# JHZ-E01S-HW-Drive-HI-S0_1-.net
KiCad netlist of a schematic drawn in Altium Designer
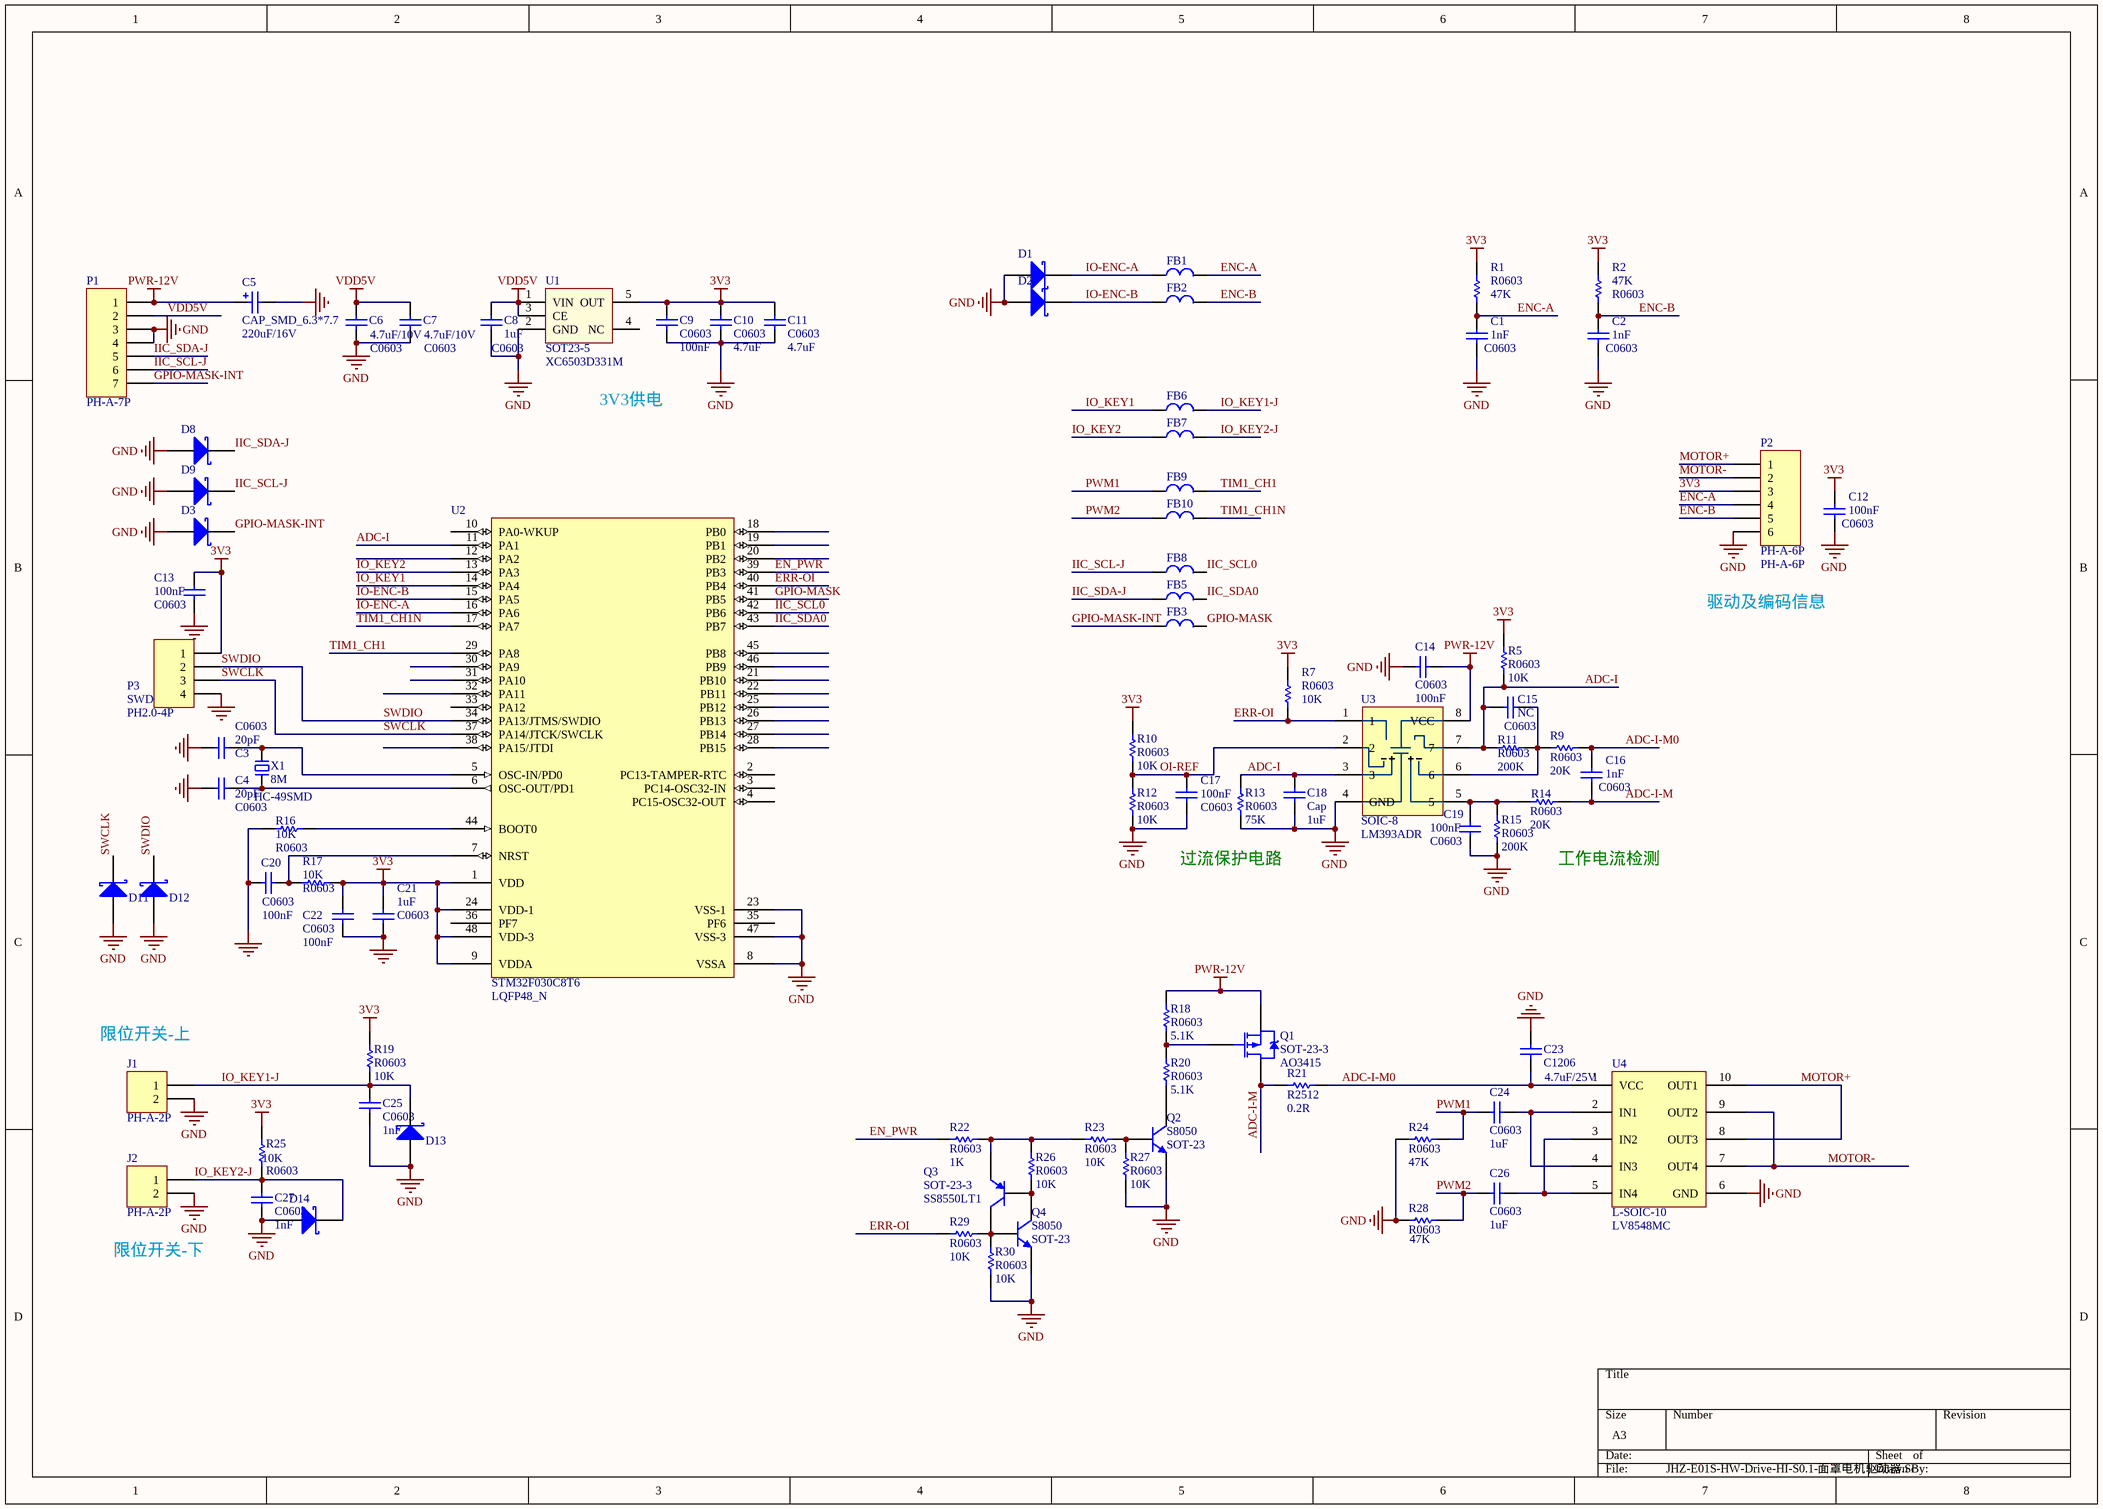
[diagram p0: JHZ-E01S-HW-Drive-HI-S0.1-面罩电机驱动器.SchDoc]

(export (version "E")
  (design (tool "Eeschema 10.0.6"))
  (components
    (comp (ref "C1")
      (value "C0603")
      (footprint "C0603_M1608")
      (description "Multilayer Ceramic Capacitor 0603")
      (fields (field (name "ALTIUM_VALUE") "1nF"))
      (libsource (lib "1.电阻、电容、电感原理库") (part "MCC0603"))
    )
    (comp (ref "C2")
      (value "C0603")
      (footprint "C0603_M1608")
      (description "Multilayer Ceramic Capacitor 0603")
      (fields (field (name "ALTIUM_VALUE") "1nF"))
      (libsource (lib "1.电阻、电容、电感原理库") (part "MCC0603"))
    )
    (comp (ref "C3")
      (value "C0603")
      (footprint "C0603_M1608")
      (description "Capacitor")
      (fields (field (name "ALTIUM_VALUE") "20pF") (field (name "PUBLISHER") "Altium Limited"))
      (libsource (lib "Miscellaneous Devices") (part "Cap"))
    )
    (comp (ref "C4")
      (value "C0603")
      (footprint "C0603_M1608")
      (description "Capacitor")
      (fields (field (name "ALTIUM_VALUE") "20pF") (field (name "PUBLISHER") "Altium Limited"))
      (libsource (lib "Miscellaneous Devices") (part "Cap"))
    )
    (comp (ref "C5")
      (value "CAP_SMD_6.3*7.7")
      (footprint "CAP_SMD_6.3*7.7")
      (description "SMD Capacitor 6.3*7.7")
      (fields (field (name "ALTIUM_VALUE") "220uF/16V"))
      (libsource (lib "1.电阻、电容、电感原理库") (part "CAP_SMD_6.3*7.7"))
    )
    (comp (ref "C6")
      (value "C0603")
      (footprint "C0603_M1608")
      (description "Capacitor")
      (fields (field (name "ALTIUM_VALUE") "4.7uF/10V") (field (name "PUBLISHER") "Altium Limited"))
      (libsource (lib "Miscellaneous Devices") (part "Cap"))
    )
    (comp (ref "C7")
      (value "C0603")
      (footprint "C0603_M1608")
      (description "Capacitor")
      (fields (field (name "ALTIUM_VALUE") "4.7uF/10V") (field (name "PUBLISHER") "Altium Limited"))
      (libsource (lib "Miscellaneous Devices") (part "Cap"))
    )
    (comp (ref "C8")
      (value "C0603")
      (footprint "C0603_M1608")
      (description "Capacitor")
      (fields (field (name "ALTIUM_VALUE") "1uF") (field (name "PUBLISHER") "Altium Limited"))
      (libsource (lib "Miscellaneous Devices") (part "Cap"))
    )
    (comp (ref "C9")
      (value "C0603")
      (footprint "C0603_M1608")
      (description "Capacitor")
      (fields (field (name "ALTIUM_VALUE") "100nF") (field (name "PUBLISHER") "Altium Limited"))
      (libsource (lib "Miscellaneous Devices") (part "Cap"))
    )
    (comp (ref "C10")
      (value "C0603")
      (footprint "C0603_M1608")
      (description "Capacitor")
      (fields (field (name "ALTIUM_VALUE") "4.7uF") (field (name "PUBLISHER") "Altium Limited"))
      (libsource (lib "Miscellaneous Devices") (part "Cap"))
    )
    (comp (ref "C11")
      (value "C0603")
      (footprint "C0603_M1608")
      (description "Capacitor")
      (fields (field (name "ALTIUM_VALUE") "4.7uF") (field (name "PUBLISHER") "Altium Limited"))
      (libsource (lib "Miscellaneous Devices") (part "Cap"))
    )
    (comp (ref "C12")
      (value "C0603")
      (footprint "C0603_M1608")
      (description "Multilayer Ceramic Capacitor 0603")
      (fields (field (name "ALTIUM_VALUE") "100nF"))
      (libsource (lib "1.电阻、电容、电感原理库") (part "MCC0603"))
    )
    (comp (ref "C13")
      (value "C0603")
      (footprint "C0603_M1608")
      (description "Capacitor")
      (fields (field (name "ALTIUM_VALUE") "100nF") (field (name "PUBLISHER") "Altium Limited"))
      (libsource (lib "Miscellaneous Devices") (part "Cap"))
    )
    (comp (ref "C14")
      (value "C0603")
      (footprint "C0603_M1608")
      (description "Multilayer Ceramic Capacitor 0603")
      (fields (field (name "ALTIUM_VALUE") "100nF"))
      (libsource (lib "1.电阻、电容、电感原理库") (part "MCC0603"))
    )
    (comp (ref "C15")
      (value "C0603")
      (footprint "C0603_M1608")
      (description "Multilayer Ceramic Capacitor 0603")
      (fields (field (name "ALTIUM_VALUE") "NC"))
      (libsource (lib "1.电阻、电容、电感原理库") (part "MCC0603"))
    )
    (comp (ref "C16")
      (value "C0603")
      (footprint "C0603_M1608")
      (description "Multilayer Ceramic Capacitor 0603")
      (fields (field (name "ALTIUM_VALUE") "1nF"))
      (libsource (lib "1.电阻、电容、电感原理库") (part "MCC0603"))
    )
    (comp (ref "C17")
      (value "C0603")
      (footprint "C0603_M1608")
      (description "Multilayer Ceramic Capacitor 0603")
      (fields (field (name "ALTIUM_VALUE") "100nF"))
      (libsource (lib "1.电阻、电容、电感原理库") (part "MCC0603"))
    )
    (comp (ref "C18")
      (value "Cap")
      (footprint "C0603_M1608")
      (description "Capacitor")
      (fields (field (name "ALTIUM_VALUE") "1uF") (field (name "PUBLISHER") "Altium Limited"))
      (libsource (lib "Miscellaneous Devices") (part "Cap"))
    )
    (comp (ref "C19")
      (value "C0603")
      (footprint "C0603_M1608")
      (description "Multilayer Ceramic Capacitor 0603")
      (fields (field (name "ALTIUM_VALUE") "100nF"))
      (libsource (lib "1.电阻、电容、电感原理库") (part "MCC0603"))
    )
    (comp (ref "C20")
      (value "C0603")
      (footprint "C0603_M1608")
      (description "Capacitor")
      (fields (field (name "ALTIUM_VALUE") "100nF") (field (name "PUBLISHER") "Altium Limited"))
      (libsource (lib "Miscellaneous Devices") (part "Cap"))
    )
    (comp (ref "C21")
      (value "C0603")
      (footprint "C0603_M1608")
      (description "Capacitor")
      (fields (field (name "ALTIUM_VALUE") "1uF") (field (name "PUBLISHER") "Altium Limited"))
      (libsource (lib "Miscellaneous Devices") (part "Cap"))
    )
    (comp (ref "C22")
      (value "C0603")
      (footprint "C0603_M1608")
      (description "Capacitor")
      (fields (field (name "ALTIUM_VALUE") "100nF") (field (name "PUBLISHER") "Altium Limited"))
      (libsource (lib "Miscellaneous Devices") (part "Cap"))
    )
    (comp (ref "C23")
      (value "C1206")
      (footprint "C1206_M3216")
      (description "Capacitor")
      (fields (field (name "ALTIUM_VALUE") "4.7uF/25V") (field (name "PUBLISHER") "Altium Limited"))
      (libsource (lib "Miscellaneous Devices") (part "Cap"))
    )
    (comp (ref "C24")
      (value "C0603")
      (footprint "C0603_M1608")
      (description "Capacitor")
      (fields (field (name "ALTIUM_VALUE") "1uF") (field (name "PUBLISHER") "Altium Limited"))
      (libsource (lib "Miscellaneous Devices") (part "Cap"))
    )
    (comp (ref "C25")
      (value "C0603")
      (footprint "C0603_M1608")
      (description "Capacitor")
      (fields (field (name "ALTIUM_VALUE") "1nF") (field (name "PUBLISHER") "Altium Limited"))
      (libsource (lib "Miscellaneous Devices") (part "Cap"))
    )
    (comp (ref "C26")
      (value "C0603")
      (footprint "C0603_M1608")
      (description "Capacitor")
      (fields (field (name "ALTIUM_VALUE") "1uF") (field (name "PUBLISHER") "Altium Limited"))
      (libsource (lib "Miscellaneous Devices") (part "Cap"))
    )
    (comp (ref "C27")
      (value "C0603")
      (footprint "C0603_M1608")
      (description "Capacitor")
      (fields (field (name "ALTIUM_VALUE") "1nF") (field (name "PUBLISHER") "Altium Limited"))
      (libsource (lib "Miscellaneous Devices") (part "Cap"))
    )
    (comp (ref "D1")
      (value "SOD-523")
      (footprint "SOD-523")
      (description "2.0A SURFACE MOUNT SCHOTTKY BARRIER  RECTIFIERS")
      (libsource (lib "2.二极管原理库") (part "SK2B"))
    )
    (comp (ref "D2")
      (value "SOD-523")
      (footprint "SOD-523")
      (description "2.0A SURFACE MOUNT SCHOTTKY BARRIER  RECTIFIERS")
      (libsource (lib "2.二极管原理库") (part "SK2B"))
    )
    (comp (ref "D3")
      (value "SOD-523")
      (footprint "SOD-523")
      (description "2.0A SURFACE MOUNT SCHOTTKY BARRIER  RECTIFIERS")
      (libsource (lib "2.二极管原理库") (part "SK2B"))
    )
    (comp (ref "D8")
      (value "SOD-523")
      (footprint "SOD-523")
      (description "2.0A SURFACE MOUNT SCHOTTKY BARRIER  RECTIFIERS")
      (libsource (lib "2.二极管原理库") (part "SK2B"))
    )
    (comp (ref "D9")
      (value "SOD-523")
      (footprint "SOD-523")
      (description "2.0A SURFACE MOUNT SCHOTTKY BARRIER  RECTIFIERS")
      (libsource (lib "2.二极管原理库") (part "SK2B"))
    )
    (comp (ref "D11")
      (value "SOD-523")
      (footprint "SOD-523")
      (description "2.0A SURFACE MOUNT SCHOTTKY BARRIER  RECTIFIERS")
      (libsource (lib "2.二极管原理库") (part "SK2B"))
    )
    (comp (ref "D12")
      (value "SOD-523")
      (footprint "SOD-523")
      (description "2.0A SURFACE MOUNT SCHOTTKY BARRIER  RECTIFIERS")
      (libsource (lib "2.二极管原理库") (part "SK2B"))
    )
    (comp (ref "D13")
      (value "SOD-523")
      (footprint "SOD-523")
      (description "2.0A SURFACE MOUNT SCHOTTKY BARRIER  RECTIFIERS")
      (libsource (lib "2.二极管原理库") (part "SK2B"))
    )
    (comp (ref "D14")
      (value "SOD-523")
      (footprint "SOD-523")
      (description "2.0A SURFACE MOUNT SCHOTTKY BARRIER  RECTIFIERS")
      (libsource (lib "2.二极管原理库") (part "SK2B"))
    )
    (comp (ref "FB1")
      (value "FBM1608-0E0PT")
      (footprint "R0603_M1608")
      (description "磁珠Ferrite Bead")
      (libsource (lib "1.电阻、电容、电感原理库") (part "FBM1608-0E0PT"))
    )
    (comp (ref "FB2")
      (value "FBM1608-0E0PT")
      (footprint "R0603_M1608")
      (description "磁珠Ferrite Bead")
      (libsource (lib "1.电阻、电容、电感原理库") (part "FBM1608-0E0PT"))
    )
    (comp (ref "FB3")
      (value "FBM1608-0E0PT")
      (footprint "R0603_M1608")
      (description "磁珠Ferrite Bead")
      (libsource (lib "1.电阻、电容、电感原理库") (part "FBM1608-0E0PT"))
    )
    (comp (ref "FB5")
      (value "FBM1608-0E0PT")
      (footprint "R0603_M1608")
      (description "磁珠Ferrite Bead")
      (libsource (lib "1.电阻、电容、电感原理库") (part "FBM1608-0E0PT"))
    )
    (comp (ref "FB6")
      (value "FBM1608-0E0PT")
      (footprint "R0603_M1608")
      (description "磁珠Ferrite Bead")
      (libsource (lib "1.电阻、电容、电感原理库") (part "FBM1608-0E0PT"))
    )
    (comp (ref "FB7")
      (value "FBM1608-0E0PT")
      (footprint "R0603_M1608")
      (description "磁珠Ferrite Bead")
      (libsource (lib "1.电阻、电容、电感原理库") (part "FBM1608-0E0PT"))
    )
    (comp (ref "FB8")
      (value "FBM1608-0E0PT")
      (footprint "R0603_M1608")
      (description "磁珠Ferrite Bead")
      (libsource (lib "1.电阻、电容、电感原理库") (part "FBM1608-0E0PT"))
    )
    (comp (ref "FB9")
      (value "FBM1608-0E0PT")
      (footprint "R0603_M1608")
      (description "磁珠Ferrite Bead")
      (libsource (lib "1.电阻、电容、电感原理库") (part "FBM1608-0E0PT"))
    )
    (comp (ref "FB10")
      (value "FBM1608-0E0PT")
      (footprint "R0603_M1608")
      (description "磁珠Ferrite Bead")
      (libsource (lib "1.电阻、电容、电感原理库") (part "FBM1608-0E0PT"))
    )
    (comp (ref "J1")
      (value "PH-A-2P")
      (footprint "PH-A-2P")
      (description "Header, 2.0mm,2-Pin")
      (libsource (lib "7.PH XH VH KF2510连接器原理库") (part "PH-A-2P"))
    )
    (comp (ref "J2")
      (value "PH-A-2P")
      (footprint "PH-A-2P")
      (description "Header, 2.0mm,2-Pin")
      (libsource (lib "7.PH XH VH KF2510连接器原理库") (part "PH-A-2P"))
    )
    (comp (ref "P1")
      (value "PH-A-7P")
      (footprint "PH-A-7P")
      (description "Header, 2.0mm,7-Pin")
      (libsource (lib "7.PH XH VH KF2510连接器原理库") (part "PH-A-7P"))
    )
    (comp (ref "P2")
      (value "PH-A-6P")
      (footprint "PH-A-6P")
      (description "Header, 2.0mm,6-Pin")
      (fields (field (name "ALTIUM_VALUE") "PH-A-6P"))
      (libsource (lib "7.PH XH VH KF2510连接器原理库") (part "PH-A-6P"))
    )
    (comp (ref "P3")
      (value "PH2.0-4P")
      (footprint "PH-A-4P")
      (description "Header, 4-Pin")
      (fields (field (name "ALTIUM_VALUE") "SWD") (field (name "PUBLISHER") "Altium Limited"))
      (libsource (lib "Miscellaneous Connectors") (part "Header 4"))
    )
    (comp (ref "Q1")
      (value "SOT-23-3")
      (footprint "SOT-23-3")
      (description "P-Channel MOSFET")
      (fields (field (name "ALTIUM_VALUE") "AO3415"))
      (libsource (lib "3.三极管原理库") (part "AO3415"))
    )
    (comp (ref "Q2")
      (value "SOT-23")
      (footprint "SOT-23_L")
      (description "NPN Bipolar Transistor")
      (fields (field (name "ALTIUM_VALUE") "S8050") (field (name "PUBLISHER") "Altium Limited"))
      (libsource (lib "CYSchlib") (part "NPN"))
    )
    (comp (ref "Q3")
      (value "SOT-23-3")
      (footprint "SOT-23-3")
      (description "PNP Bipolar Transistor")
      (fields (field (name "ALTIUM_VALUE") "SS8550LT1"))
      (libsource (lib "3.三极管原理库") (part "SS8550LT1"))
    )
    (comp (ref "Q4")
      (value "SOT-23")
      (footprint "SOT-23_L")
      (description "NPN Bipolar Transistor")
      (fields (field (name "ALTIUM_VALUE") "S8050") (field (name "PUBLISHER") "Altium Limited"))
      (libsource (lib "CYSchlib") (part "NPN"))
    )
    (comp (ref "R1")
      (value "R0603")
      (footprint "R0603_M1608")
      (description "Resistor")
      (fields (field (name "ALTIUM_VALUE") "47K") (field (name "PUBLISHER") "Altium Limited"))
      (libsource (lib "Miscellaneous Devices") (part "Res1"))
    )
    (comp (ref "R2")
      (value "R0603")
      (footprint "R0603_M1608")
      (description "Resistor")
      (fields (field (name "ALTIUM_VALUE") "47K") (field (name "PUBLISHER") "Altium Limited"))
      (libsource (lib "Miscellaneous Devices") (part "Res1"))
    )
    (comp (ref "R5")
      (value "R0603")
      (footprint "R0603_M1608")
      (description "Resistor")
      (fields (field (name "ALTIUM_VALUE") "10K"))
      (libsource (lib "1.电阻、电容、电感原理库") (part "R0603_M1608"))
    )
    (comp (ref "R7")
      (value "R0603")
      (description "Resistor")
      (fields (field (name "ALTIUM_VALUE") "10K") (field (name "PUBLISHER") "Altium Limited"))
      (libsource (lib "Miscellaneous Devices") (part "Res1"))
    )
    (comp (ref "R9")
      (value "R0603")
      (footprint "R0603_M1608")
      (description "Resistor")
      (fields (field (name "ALTIUM_VALUE") "20K"))
      (libsource (lib "1.电阻、电容、电感原理库") (part "R0603_M1608"))
    )
    (comp (ref "R10")
      (value "R0603")
      (footprint "R0603_M1608")
      (description "Resistor")
      (fields (field (name "ALTIUM_VALUE") "10K"))
      (libsource (lib "1.电阻、电容、电感原理库") (part "R0603_M1608"))
    )
    (comp (ref "R11")
      (value "R0603")
      (footprint "R0603_M1608")
      (description "Resistor")
      (fields (field (name "ALTIUM_VALUE") "200K"))
      (libsource (lib "1.电阻、电容、电感原理库") (part "R0603_M1608"))
    )
    (comp (ref "R12")
      (value "R0603")
      (footprint "R0603_M1608")
      (description "Resistor")
      (fields (field (name "ALTIUM_VALUE") "10K"))
      (libsource (lib "1.电阻、电容、电感原理库") (part "R0603_M1608"))
    )
    (comp (ref "R13")
      (value "R0603")
      (footprint "R0603_M1608")
      (description "Resistor")
      (fields (field (name "ALTIUM_VALUE") "75K"))
      (libsource (lib "1.电阻、电容、电感原理库") (part "R0603_M1608"))
    )
    (comp (ref "R14")
      (value "R0603")
      (footprint "R0603_M1608")
      (description "Resistor")
      (fields (field (name "ALTIUM_VALUE") "20K"))
      (libsource (lib "1.电阻、电容、电感原理库") (part "R0603_M1608"))
    )
    (comp (ref "R15")
      (value "R0603")
      (footprint "R0603_M1608")
      (description "Resistor")
      (fields (field (name "ALTIUM_VALUE") "200K"))
      (libsource (lib "1.电阻、电容、电感原理库") (part "R0603_M1608"))
    )
    (comp (ref "R16")
      (value "R0603")
      (footprint "R0603_M1608")
      (description "Resistor")
      (fields (field (name "ALTIUM_VALUE") "10K") (field (name "PUBLISHER") "Altium Limited"))
      (libsource (lib "Miscellaneous Devices") (part "Res1"))
    )
    (comp (ref "R17")
      (value "R0603")
      (footprint "R0603_M1608")
      (description "Resistor")
      (fields (field (name "ALTIUM_VALUE") "10K") (field (name "PUBLISHER") "Altium Limited"))
      (libsource (lib "Miscellaneous Devices") (part "Res1"))
    )
    (comp (ref "R18")
      (value "R0603")
      (footprint "R0603_M1608")
      (description "Resistor")
      (fields (field (name "ALTIUM_VALUE") "5.1K") (field (name "PUBLISHER") "Altium Limited"))
      (libsource (lib "Miscellaneous Devices") (part "Res1"))
    )
    (comp (ref "R19")
      (value "R0603")
      (footprint "R0603_M1608")
      (description "Resistor")
      (fields (field (name "ALTIUM_VALUE") "10K") (field (name "PUBLISHER") "Altium Limited"))
      (libsource (lib "Miscellaneous Devices") (part "Res1"))
    )
    (comp (ref "R20")
      (value "R0603")
      (footprint "R0603_M1608")
      (description "Resistor")
      (fields (field (name "ALTIUM_VALUE") "5.1K") (field (name "PUBLISHER") "Altium Limited"))
      (libsource (lib "Miscellaneous Devices") (part "Res1"))
    )
    (comp (ref "R21")
      (value "R2512")
      (footprint "R2512_M6332")
      (description "Resistor")
      (fields (field (name "ALTIUM_VALUE") "0.2R") (field (name "PUBLISHER") "Altium Limited"))
      (libsource (lib "Miscellaneous Devices") (part "Res1"))
    )
    (comp (ref "R22")
      (value "R0603")
      (footprint "R0603_M1608")
      (description "Resistor")
      (fields (field (name "ALTIUM_VALUE") "1K") (field (name "PUBLISHER") "Altium Limited"))
      (libsource (lib "Miscellaneous Devices") (part "Res1"))
    )
    (comp (ref "R23")
      (value "R0603")
      (footprint "R0603_M1608")
      (description "Resistor")
      (fields (field (name "ALTIUM_VALUE") "10K") (field (name "PUBLISHER") "Altium Limited"))
      (libsource (lib "Miscellaneous Devices") (part "Res1"))
    )
    (comp (ref "R24")
      (value "R0603")
      (footprint "R0603_M1608")
      (description "Resistor")
      (fields (field (name "ALTIUM_VALUE") "47K") (field (name "PUBLISHER") "Altium Limited"))
      (libsource (lib "Miscellaneous Devices") (part "Res1"))
    )
    (comp (ref "R25")
      (value "R0603")
      (footprint "R0603_M1608")
      (description "Resistor")
      (fields (field (name "ALTIUM_VALUE") "10K") (field (name "PUBLISHER") "Altium Limited"))
      (libsource (lib "Miscellaneous Devices") (part "Res1"))
    )
    (comp (ref "R26")
      (value "R0603")
      (footprint "R0603_M1608")
      (description "Resistor")
      (fields (field (name "ALTIUM_VALUE") "10K") (field (name "PUBLISHER") "Altium Limited"))
      (libsource (lib "Miscellaneous Devices") (part "Res1"))
    )
    (comp (ref "R27")
      (value "R0603")
      (footprint "R0603_M1608")
      (description "Resistor")
      (fields (field (name "ALTIUM_VALUE") "10K") (field (name "PUBLISHER") "Altium Limited"))
      (libsource (lib "Miscellaneous Devices") (part "Res1"))
    )
    (comp (ref "R28")
      (value "R0603")
      (footprint "R0603_M1608")
      (description "Resistor")
      (fields (field (name "ALTIUM_VALUE") "47K") (field (name "PUBLISHER") "Altium Limited"))
      (libsource (lib "Miscellaneous Devices") (part "Res1"))
    )
    (comp (ref "R29")
      (value "R0603")
      (footprint "R0603_M1608")
      (description "Resistor")
      (fields (field (name "ALTIUM_VALUE") "10K") (field (name "PUBLISHER") "Altium Limited"))
      (libsource (lib "Miscellaneous Devices") (part "Res1"))
    )
    (comp (ref "R30")
      (value "R0603")
      (footprint "R0603_M1608")
      (description "Resistor")
      (fields (field (name "ALTIUM_VALUE") "10K") (field (name "PUBLISHER") "Altium Limited"))
      (libsource (lib "Miscellaneous Devices") (part "Res1"))
    )
    (comp (ref "U1")
      (value "SOT23-5")
      (footprint "SOT-23-5")
      (fields (field (name "ALTIUM_VALUE") "XC6503D331M"))
      (libsource (lib "SCH") (part "XC6503D301MR"))
    )
    (comp (ref "U2")
      (value "LQFP48_N")
      (footprint "LQFP48_N")
      (description "STM32 ARM-based 32-bit MCU with 64 Kbytes Flash, 48-pin LQFP, Industrial Temperature")
      (fields (field (name "ALTIUM_VALUE") "STM32F030C8T6") (field (name "PUBLISHER") "*"))
      (libsource (lib "ST Microcontroller 32-Bit STM32 SCH") (part "STM32F103C8T6"))
    )
    (comp (ref "U3")
      (value "SOIC-8")
      (footprint "SOIC-8")
      (description "Dual Operational Amplifiers")
      (fields (field (name "ALTIUM_VALUE") "LM393ADR"))
      (libsource (lib "5.芯片原理库") (part "LM358ADR"))
    )
    (comp (ref "U4")
      (value "L-SOIC-10")
      (footprint "L-SOIC-10")
      (fields (field (name "ALTIUM_VALUE") "LV8548MC"))
      (libsource (lib "Schlib1") (part "LV8548MC"))
    )
    (comp (ref "X1")
      (value "8M")
      (footprint "HC-49SMD")
      (fields (field (name "ALTIUM_VALUE") "HC-49SMD"))
      (libsource (lib "CYSchlib") (part "XTAL"))
    )
  )
  (nets
    (net (code "1") (name "/ADC-I") (class "Default")
      (node (ref "C15") (pin "2") (pinfunction "2_2") (pintype "passive"))
      (node (ref "C18") (pin "2") (pinfunction "2_2") (pintype "passive"))
      (node (ref "R11") (pin "1") (pinfunction "1_1") (pintype "passive"))
      (node (ref "R13") (pin "2") (pinfunction "2_2") (pintype "passive"))
      (node (ref "R5") (pin "2") (pinfunction "2_2") (pintype "passive"))
      (node (ref "U2") (pin "11") (pinfunction "PA1_11") (pintype "bidirectional"))
      (node (ref "U3") (pin "3") (pinfunction "3_3") (pintype "passive"))
      (node (ref "U3") (pin "7") (pinfunction "7_7") (pintype "passive"))
    )
    (net (code "2") (name "/ADC-I-M") (class "Default")
      (node (ref "C16") (pin "1") (pinfunction "1_1") (pintype "passive"))
      (node (ref "Q1") (pin "3") (pinfunction "D_3") (pintype "passive"))
      (node (ref "R14") (pin "1") (pinfunction "1_1") (pintype "passive"))
      (node (ref "R21") (pin "1") (pinfunction "1_1") (pintype "passive"))
    )
    (net (code "3") (name "/ADC-I-M0") (class "Default")
      (node (ref "C16") (pin "2") (pinfunction "2_2") (pintype "passive"))
      (node (ref "C23") (pin "1") (pinfunction "1_1") (pintype "passive"))
      (node (ref "R21") (pin "2") (pinfunction "2_2") (pintype "passive"))
      (node (ref "R9") (pin "1") (pinfunction "1_1") (pintype "passive"))
      (node (ref "U4") (pin "1") (pinfunction "VCC_1") (pintype "passive"))
    )
    (net (code "4") (name "/ENC-A") (class "Default")
      (node (ref "C1") (pin "1") (pinfunction "1_1") (pintype "passive"))
      (node (ref "FB1") (pin "2") (pinfunction "2_2") (pintype "passive"))
      (node (ref "P2") (pin "4") (pinfunction "4_4") (pintype "passive"))
      (node (ref "R1") (pin "1") (pinfunction "1_1") (pintype "passive"))
    )
    (net (code "5") (name "/ENC-B") (class "Default")
      (node (ref "C2") (pin "1") (pinfunction "1_1") (pintype "passive"))
      (node (ref "FB2") (pin "2") (pinfunction "2_2") (pintype "passive"))
      (node (ref "P2") (pin "5") (pinfunction "5_5") (pintype "passive"))
      (node (ref "R2") (pin "1") (pinfunction "1_1") (pintype "passive"))
    )
    (net (code "6") (name "/EN_PWR") (class "Default")
      (node (ref "R22") (pin "2") (pinfunction "2_2") (pintype "passive"))
      (node (ref "U2") (pin "39") (pinfunction "PB3_39") (pintype "bidirectional"))
    )
    (net (code "7") (name "/ERR-OI") (class "Default")
      (node (ref "R29") (pin "2") (pinfunction "2_2") (pintype "passive"))
      (node (ref "R7") (pin "1") (pinfunction "1_1") (pintype "passive"))
      (node (ref "U2") (pin "40") (pinfunction "PB4_40") (pintype "bidirectional"))
      (node (ref "U3") (pin "1") (pinfunction "1_1") (pintype "passive"))
    )
    (net (code "8") (name "/GPIO-MASK") (class "Default")
      (node (ref "FB3") (pin "2") (pinfunction "2_2") (pintype "passive"))
      (node (ref "U2") (pin "41") (pinfunction "PB5_41") (pintype "bidirectional"))
    )
    (net (code "9") (name "/GPIO-MASK-INT") (class "Default")
      (node (ref "D3") (pin "2") (pinfunction "K_2") (pintype "passive"))
      (node (ref "FB3") (pin "1") (pinfunction "1_1") (pintype "passive"))
      (node (ref "P1") (pin "7") (pinfunction "7_7") (pintype "passive"))
    )
    (net (code "10") (name "/IIC_SCL-J") (class "Default")
      (node (ref "D9") (pin "2") (pinfunction "K_2") (pintype "passive"))
      (node (ref "FB8") (pin "1") (pinfunction "1_1") (pintype "passive"))
      (node (ref "P1") (pin "6") (pinfunction "6_6") (pintype "passive"))
    )
    (net (code "11") (name "/IIC_SCL0") (class "Default")
      (node (ref "FB8") (pin "2") (pinfunction "2_2") (pintype "passive"))
      (node (ref "U2") (pin "42") (pinfunction "PB6_42") (pintype "bidirectional"))
    )
    (net (code "12") (name "/IIC_SDA-J") (class "Default")
      (node (ref "D8") (pin "2") (pinfunction "K_2") (pintype "passive"))
      (node (ref "FB5") (pin "1") (pinfunction "1_1") (pintype "passive"))
      (node (ref "P1") (pin "5") (pinfunction "5_5") (pintype "passive"))
    )
    (net (code "13") (name "/IIC_SDA0") (class "Default")
      (node (ref "FB5") (pin "2") (pinfunction "2_2") (pintype "passive"))
      (node (ref "U2") (pin "43") (pinfunction "PB7_43") (pintype "bidirectional"))
    )
    (net (code "14") (name "/IO-ENC-A") (class "Default")
      (node (ref "D1") (pin "2") (pinfunction "K_2") (pintype "passive"))
      (node (ref "FB1") (pin "1") (pinfunction "1_1") (pintype "passive"))
      (node (ref "U2") (pin "16") (pinfunction "PA6_16") (pintype "bidirectional"))
    )
    (net (code "15") (name "/IO-ENC-B") (class "Default")
      (node (ref "D2") (pin "2") (pinfunction "K_2") (pintype "passive"))
      (node (ref "FB2") (pin "1") (pinfunction "1_1") (pintype "passive"))
      (node (ref "U2") (pin "15") (pinfunction "PA5_15") (pintype "bidirectional"))
    )
    (net (code "16") (name "/IO_KEY1") (class "Default")
      (node (ref "FB6") (pin "1") (pinfunction "1_1") (pintype "passive"))
      (node (ref "U2") (pin "14") (pinfunction "PA4_14") (pintype "bidirectional"))
    )
    (net (code "17") (name "/IO_KEY1-J") (class "Default")
      (node (ref "C25") (pin "2") (pinfunction "2_2") (pintype "passive"))
      (node (ref "D13") (pin "2") (pinfunction "K_2") (pintype "passive"))
      (node (ref "FB6") (pin "2") (pinfunction "2_2") (pintype "passive"))
      (node (ref "J1") (pin "1") (pinfunction "1_1") (pintype "passive"))
      (node (ref "R19") (pin "1") (pinfunction "1_1") (pintype "passive"))
    )
    (net (code "18") (name "/IO_KEY2") (class "Default")
      (node (ref "FB7") (pin "1") (pinfunction "1_1") (pintype "passive"))
      (node (ref "U2") (pin "13") (pinfunction "PA3_13") (pintype "bidirectional"))
    )
    (net (code "19") (name "/IO_KEY2-J") (class "Default")
      (node (ref "C27") (pin "2") (pinfunction "2_2") (pintype "passive"))
      (node (ref "D14") (pin "2") (pinfunction "K_2") (pintype "passive"))
      (node (ref "FB7") (pin "2") (pinfunction "2_2") (pintype "passive"))
      (node (ref "J2") (pin "1") (pinfunction "1_1") (pintype "passive"))
      (node (ref "R25") (pin "1") (pinfunction "1_1") (pintype "passive"))
    )
    (net (code "20") (name "/MOTOR+") (class "Default")
      (node (ref "P2") (pin "1") (pinfunction "1_1") (pintype "passive"))
      (node (ref "U4") (pin "10") (pinfunction "OUT1_10") (pintype "passive"))
      (node (ref "U4") (pin "8") (pinfunction "OUT3_8") (pintype "passive"))
    )
    (net (code "21") (name "/MOTOR-") (class "Default")
      (node (ref "P2") (pin "2") (pinfunction "2_2") (pintype "passive"))
      (node (ref "U4") (pin "7") (pinfunction "OUT4_7") (pintype "passive"))
      (node (ref "U4") (pin "9") (pinfunction "OUT2_9") (pintype "passive"))
    )
    (net (code "22") (name "/OI-REF") (class "Default")
      (node (ref "C17") (pin "2") (pinfunction "2_2") (pintype "passive"))
      (node (ref "R10") (pin "1") (pinfunction "1_1") (pintype "passive"))
      (node (ref "R12") (pin "2") (pinfunction "2_2") (pintype "passive"))
      (node (ref "U3") (pin "2") (pinfunction "2_2") (pintype "passive"))
    )
    (net (code "23") (name "/PWM1") (class "Default")
      (node (ref "C24") (pin "1") (pinfunction "1_1") (pintype "passive"))
      (node (ref "FB9") (pin "1") (pinfunction "1_1") (pintype "passive"))
      (node (ref "R24") (pin "1") (pinfunction "1_1") (pintype "passive"))
    )
    (net (code "24") (name "/PWM2") (class "Default")
      (node (ref "C26") (pin "1") (pinfunction "1_1") (pintype "passive"))
      (node (ref "FB10") (pin "1") (pinfunction "1_1") (pintype "passive"))
      (node (ref "R28") (pin "1") (pinfunction "1_1") (pintype "passive"))
    )
    (net (code "25") (name "/SWCLK") (class "Default")
      (node (ref "D11") (pin "2") (pinfunction "K_2") (pintype "passive"))
      (node (ref "P3") (pin "3") (pinfunction "3_3") (pintype "passive"))
      (node (ref "U2") (pin "37") (pinfunction "PA14/JTCK/SWCLK_37") (pintype "bidirectional"))
    )
    (net (code "26") (name "/SWDIO") (class "Default")
      (node (ref "D12") (pin "2") (pinfunction "K_2") (pintype "passive"))
      (node (ref "P3") (pin "2") (pinfunction "2_2") (pintype "passive"))
      (node (ref "U2") (pin "34") (pinfunction "PA13/JTMS/SWDIO_34") (pintype "bidirectional"))
    )
    (net (code "27") (name "/TIM1_CH1") (class "Default")
      (node (ref "FB9") (pin "2") (pinfunction "2_2") (pintype "passive"))
      (node (ref "U2") (pin "29") (pinfunction "PA8_29") (pintype "bidirectional"))
    )
    (net (code "28") (name "/TIM1_CH1N") (class "Default")
      (node (ref "FB10") (pin "2") (pinfunction "2_2") (pintype "passive"))
      (node (ref "U2") (pin "17") (pinfunction "PA7_17") (pintype "bidirectional"))
    )
    (net (code "29") (name "3V3") (class "Default")
      (node (ref "C10") (pin "1") (pinfunction "1_1") (pintype "passive"))
      (node (ref "C11") (pin "1") (pinfunction "1_1") (pintype "passive"))
      (node (ref "C12") (pin "1") (pinfunction "1_1") (pintype "passive"))
      (node (ref "C13") (pin "1") (pinfunction "1_1") (pintype "passive"))
      (node (ref "C21") (pin "1") (pinfunction "1_1") (pintype "passive"))
      (node (ref "C22") (pin "1") (pinfunction "1_1") (pintype "passive"))
      (node (ref "C9") (pin "1") (pinfunction "1_1") (pintype "passive"))
      (node (ref "P2") (pin "3") (pinfunction "3_3") (pintype "passive"))
      (node (ref "P3") (pin "1") (pinfunction "1_1") (pintype "passive"))
      (node (ref "R1") (pin "2") (pinfunction "2_2") (pintype "passive"))
      (node (ref "R10") (pin "2") (pinfunction "2_2") (pintype "passive"))
      (node (ref "R17") (pin "2") (pinfunction "2_2") (pintype "passive"))
      (node (ref "R19") (pin "2") (pinfunction "2_2") (pintype "passive"))
      (node (ref "R2") (pin "2") (pinfunction "2_2") (pintype "passive"))
      (node (ref "R25") (pin "2") (pinfunction "2_2") (pintype "passive"))
      (node (ref "R5") (pin "1") (pinfunction "1_1") (pintype "passive"))
      (node (ref "R7") (pin "2") (pinfunction "2_2") (pintype "passive"))
      (node (ref "U1") (pin "5") (pinfunction "OUT_5") (pintype "passive"))
      (node (ref "U2") (pin "1") (pinfunction "VDD_1") (pintype "power_in"))
      (node (ref "U2") (pin "24") (pinfunction "VDD-1_24") (pintype "power_in"))
      (node (ref "U2") (pin "48") (pinfunction "VDD-3_48") (pintype "power_in"))
      (node (ref "U2") (pin "9") (pinfunction "VDDA_9") (pintype "power_in"))
    )
    (net (code "30") (name "GND") (class "Default")
      (node (ref "C1") (pin "2") (pinfunction "2_2") (pintype "passive"))
      (node (ref "C10") (pin "2") (pinfunction "2_2") (pintype "passive"))
      (node (ref "C11") (pin "2") (pinfunction "2_2") (pintype "passive"))
      (node (ref "C12") (pin "2") (pinfunction "2_2") (pintype "passive"))
      (node (ref "C13") (pin "2") (pinfunction "2_2") (pintype "passive"))
      (node (ref "C14") (pin "2") (pinfunction "2_2") (pintype "passive"))
      (node (ref "C17") (pin "1") (pinfunction "1_1") (pintype "passive"))
      (node (ref "C18") (pin "1") (pinfunction "1_1") (pintype "passive"))
      (node (ref "C19") (pin "1") (pinfunction "1_1") (pintype "passive"))
      (node (ref "C2") (pin "2") (pinfunction "2_2") (pintype "passive"))
      (node (ref "C20") (pin "1") (pinfunction "1_1") (pintype "passive"))
      (node (ref "C21") (pin "2") (pinfunction "2_2") (pintype "passive"))
      (node (ref "C22") (pin "2") (pinfunction "2_2") (pintype "passive"))
      (node (ref "C23") (pin "2") (pinfunction "2_2") (pintype "passive"))
      (node (ref "C25") (pin "1") (pinfunction "1_1") (pintype "passive"))
      (node (ref "C27") (pin "1") (pinfunction "1_1") (pintype "passive"))
      (node (ref "C3") (pin "1") (pinfunction "1_1") (pintype "passive"))
      (node (ref "C4") (pin "1") (pinfunction "1_1") (pintype "passive"))
      (node (ref "C5") (pin "2") (pinfunction "2_2") (pintype "passive"))
      (node (ref "C6") (pin "1") (pinfunction "1_1") (pintype "passive"))
      (node (ref "C7") (pin "1") (pinfunction "1_1") (pintype "passive"))
      (node (ref "C8") (pin "1") (pinfunction "1_1") (pintype "passive"))
      (node (ref "C9") (pin "2") (pinfunction "2_2") (pintype "passive"))
      (node (ref "D1") (pin "1") (pinfunction "A_1") (pintype "passive"))
      (node (ref "D11") (pin "1") (pinfunction "A_1") (pintype "passive"))
      (node (ref "D12") (pin "1") (pinfunction "A_1") (pintype "passive"))
      (node (ref "D13") (pin "1") (pinfunction "A_1") (pintype "passive"))
      (node (ref "D14") (pin "1") (pinfunction "A_1") (pintype "passive"))
      (node (ref "D2") (pin "1") (pinfunction "A_1") (pintype "passive"))
      (node (ref "D3") (pin "1") (pinfunction "A_1") (pintype "passive"))
      (node (ref "D8") (pin "1") (pinfunction "A_1") (pintype "passive"))
      (node (ref "D9") (pin "1") (pinfunction "A_1") (pintype "passive"))
      (node (ref "J1") (pin "2") (pinfunction "2_2") (pintype "passive"))
      (node (ref "J2") (pin "2") (pinfunction "2_2") (pintype "passive"))
      (node (ref "P1") (pin "3") (pinfunction "3_3") (pintype "passive"))
      (node (ref "P1") (pin "4") (pinfunction "4_4") (pintype "passive"))
      (node (ref "P2") (pin "6") (pinfunction "6_6") (pintype "passive"))
      (node (ref "P3") (pin "4") (pinfunction "4_4") (pintype "passive"))
      (node (ref "Q2") (pin "2") (pinfunction "E_2") (pintype "passive"))
      (node (ref "Q4") (pin "2") (pinfunction "E_2") (pintype "passive"))
      (node (ref "R12") (pin "1") (pinfunction "1_1") (pintype "passive"))
      (node (ref "R13") (pin "1") (pinfunction "1_1") (pintype "passive"))
      (node (ref "R15") (pin "1") (pinfunction "1_1") (pintype "passive"))
      (node (ref "R16") (pin "1") (pinfunction "1_1") (pintype "passive"))
      (node (ref "R24") (pin "2") (pinfunction "2_2") (pintype "passive"))
      (node (ref "R27") (pin "1") (pinfunction "1_1") (pintype "passive"))
      (node (ref "R28") (pin "2") (pinfunction "2_2") (pintype "passive"))
      (node (ref "R30") (pin "1") (pinfunction "1_1") (pintype "passive"))
      (node (ref "U1") (pin "2") (pinfunction "GND_2") (pintype "passive"))
      (node (ref "U2") (pin "23") (pinfunction "VSS-1_23") (pintype "power_in"))
      (node (ref "U2") (pin "47") (pinfunction "VSS-3_47") (pintype "power_in"))
      (node (ref "U2") (pin "8") (pinfunction "VSSA_8") (pintype "power_in"))
      (node (ref "U3") (pin "4") (pinfunction "GND_4") (pintype "passive"))
      (node (ref "U4") (pin "6") (pinfunction "GND_6") (pintype "passive"))
    )
    (net (code "31") (name "Net-(C15-Pad1)") (class "Default")
      (node (ref "C15") (pin "1") (pinfunction "1_1") (pintype "passive"))
      (node (ref "R11") (pin "2") (pinfunction "2_2") (pintype "passive"))
      (node (ref "R9") (pin "2") (pinfunction "2_2") (pintype "passive"))
      (node (ref "U3") (pin "6") (pinfunction "6_6") (pintype "passive"))
    )
    (net (code "32") (name "Net-(C19-Pad2)") (class "Default")
      (node (ref "C19") (pin "2") (pinfunction "2_2") (pintype "passive"))
      (node (ref "R14") (pin "2") (pinfunction "2_2") (pintype "passive"))
      (node (ref "R15") (pin "2") (pinfunction "2_2") (pintype "passive"))
      (node (ref "U3") (pin "5") (pinfunction "5_5") (pintype "passive"))
    )
    (net (code "33") (name "Net-(Q1-G)") (class "Default")
      (node (ref "Q1") (pin "1") (pinfunction "G_1") (pintype "passive"))
      (node (ref "R18") (pin "1") (pinfunction "1_1") (pintype "passive"))
      (node (ref "R20") (pin "2") (pinfunction "2_2") (pintype "passive"))
    )
    (net (code "34") (name "Net-(Q2-B)") (class "Default")
      (node (ref "Q2") (pin "1") (pinfunction "B_1") (pintype "passive"))
      (node (ref "R23") (pin "1") (pinfunction "1_1") (pintype "passive"))
      (node (ref "R27") (pin "2") (pinfunction "2_2") (pintype "passive"))
    )
    (net (code "35") (name "Net-(Q2-C)") (class "Default")
      (node (ref "Q2") (pin "3") (pinfunction "C_3") (pintype "passive"))
      (node (ref "R20") (pin "1") (pinfunction "1_1") (pintype "passive"))
    )
    (net (code "36") (name "Net-(Q3-B)") (class "Default")
      (node (ref "Q3") (pin "1") (pinfunction "B_1") (pintype "passive"))
      (node (ref "Q4") (pin "3") (pinfunction "C_3") (pintype "passive"))
      (node (ref "R26") (pin "1") (pinfunction "1_1") (pintype "passive"))
    )
    (net (code "37") (name "Net-(Q3-C)") (class "Default")
      (node (ref "Q3") (pin "3") (pinfunction "C_3") (pintype "passive"))
      (node (ref "Q4") (pin "1") (pinfunction "B_1") (pintype "passive"))
      (node (ref "R29") (pin "1") (pinfunction "1_1") (pintype "passive"))
      (node (ref "R30") (pin "2") (pinfunction "2_2") (pintype "passive"))
    )
    (net (code "38") (name "Net-(Q3-E)") (class "Default")
      (node (ref "Q3") (pin "2") (pinfunction "E_2") (pintype "passive"))
      (node (ref "R22") (pin "1") (pinfunction "1_1") (pintype "passive"))
      (node (ref "R23") (pin "2") (pinfunction "2_2") (pintype "passive"))
      (node (ref "R26") (pin "2") (pinfunction "2_2") (pintype "passive"))
    )
    (net (code "39") (name "Net-(U2-BOOT0)") (class "Default")
      (node (ref "R16") (pin "2") (pinfunction "2_2") (pintype "passive"))
      (node (ref "U2") (pin "44") (pinfunction "BOOT0_44") (pintype "input"))
    )
    (net (code "40") (name "Net-(U2-NRST)") (class "Default")
      (node (ref "C20") (pin "2") (pinfunction "2_2") (pintype "passive"))
      (node (ref "R17") (pin "1") (pinfunction "1_1") (pintype "passive"))
      (node (ref "U2") (pin "7") (pinfunction "NRST_7") (pintype "bidirectional"))
    )
    (net (code "41") (name "Net-(U2-OSC-IN{slash}PD0)") (class "Default")
      (node (ref "C3") (pin "2") (pinfunction "2_2") (pintype "passive"))
      (node (ref "U2") (pin "5") (pinfunction "OSC-IN/PD0_5") (pintype "input"))
      (node (ref "X1") (pin "2") (pinfunction "2_2") (pintype "passive"))
    )
    (net (code "42") (name "Net-(U2-OSC-OUT{slash}PD1)") (class "Default")
      (node (ref "C4") (pin "2") (pinfunction "2_2") (pintype "passive"))
      (node (ref "U2") (pin "6") (pinfunction "OSC-OUT/PD1_6") (pintype "output"))
      (node (ref "X1") (pin "1") (pinfunction "1_1") (pintype "passive"))
    )
    (net (code "43") (name "Net-(U4-IN1)") (class "Default")
      (node (ref "C24") (pin "2") (pinfunction "2_2") (pintype "passive"))
      (node (ref "U4") (pin "2") (pinfunction "IN1_2") (pintype "passive"))
      (node (ref "U4") (pin "4") (pinfunction "IN3_4") (pintype "passive"))
    )
    (net (code "44") (name "Net-(U4-IN2)") (class "Default")
      (node (ref "C26") (pin "2") (pinfunction "2_2") (pintype "passive"))
      (node (ref "U4") (pin "3") (pinfunction "IN2_3") (pintype "passive"))
      (node (ref "U4") (pin "5") (pinfunction "IN4_5") (pintype "passive"))
    )
    (net (code "45") (name "PWR-12V") (class "Default")
      (node (ref "C14") (pin "1") (pinfunction "1_1") (pintype "passive"))
      (node (ref "C5") (pin "1") (pinfunction "1_1") (pintype "passive"))
      (node (ref "P1") (pin "1") (pinfunction "1_1") (pintype "passive"))
      (node (ref "Q1") (pin "2") (pinfunction "S_2") (pintype "passive"))
      (node (ref "R18") (pin "2") (pinfunction "2_2") (pintype "passive"))
      (node (ref "U3") (pin "8") (pinfunction "VCC_8") (pintype "passive"))
    )
    (net (code "46") (name "VDD5V") (class "Default")
      (node (ref "C6") (pin "2") (pinfunction "2_2") (pintype "passive"))
      (node (ref "C7") (pin "2") (pinfunction "2_2") (pintype "passive"))
      (node (ref "C8") (pin "2") (pinfunction "2_2") (pintype "passive"))
      (node (ref "P1") (pin "2") (pinfunction "2_2") (pintype "passive"))
      (node (ref "U1") (pin "1") (pinfunction "VIN_1") (pintype "passive"))
      (node (ref "U1") (pin "3") (pinfunction "CE_3") (pintype "passive"))
    )
    (net (code "47") (name "unconnected-(U1-NC-Pad4)") (class "Default")
      (node (ref "U1") (pin "4") (pinfunction "NC_4") (pintype "passive"))
    )
    (net (code "48") (name "unconnected-(U2-PA0-WKUP-Pad10)") (class "Default")
      (node (ref "U2") (pin "10") (pinfunction "PA0-WKUP_10") (pintype "bidirectional"))
    )
    (net (code "49") (name "unconnected-(U2-PA2-Pad12)") (class "Default")
      (node (ref "U2") (pin "12") (pinfunction "PA2_12") (pintype "bidirectional"))
    )
    (net (code "50") (name "unconnected-(U2-PA9-Pad30)") (class "Default")
      (node (ref "U2") (pin "30") (pinfunction "PA9_30") (pintype "bidirectional"))
    )
    (net (code "51") (name "unconnected-(U2-PA10-Pad31)") (class "Default")
      (node (ref "U2") (pin "31") (pinfunction "PA10_31") (pintype "bidirectional"))
    )
    (net (code "52") (name "unconnected-(U2-PA11-Pad32)") (class "Default")
      (node (ref "U2") (pin "32") (pinfunction "PA11_32") (pintype "bidirectional"))
    )
    (net (code "53") (name "unconnected-(U2-PA12-Pad33)") (class "Default")
      (node (ref "U2") (pin "33") (pinfunction "PA12_33") (pintype "bidirectional"))
    )
    (net (code "54") (name "unconnected-(U2-PA15{slash}JTDI-Pad38)") (class "Default")
      (node (ref "U2") (pin "38") (pinfunction "PA15/JTDI_38") (pintype "bidirectional"))
    )
    (net (code "55") (name "unconnected-(U2-PB0-Pad18)") (class "Default")
      (node (ref "U2") (pin "18") (pinfunction "PB0_18") (pintype "bidirectional"))
    )
    (net (code "56") (name "unconnected-(U2-PB1-Pad19)") (class "Default")
      (node (ref "U2") (pin "19") (pinfunction "PB1_19") (pintype "bidirectional"))
    )
    (net (code "57") (name "unconnected-(U2-PB2-Pad20)") (class "Default")
      (node (ref "U2") (pin "20") (pinfunction "PB2_20") (pintype "bidirectional"))
    )
    (net (code "58") (name "unconnected-(U2-PB8-Pad45)") (class "Default")
      (node (ref "U2") (pin "45") (pinfunction "PB8_45") (pintype "bidirectional"))
    )
    (net (code "59") (name "unconnected-(U2-PB9-Pad46)") (class "Default")
      (node (ref "U2") (pin "46") (pinfunction "PB9_46") (pintype "bidirectional"))
    )
    (net (code "60") (name "unconnected-(U2-PB10-Pad21)") (class "Default")
      (node (ref "U2") (pin "21") (pinfunction "PB10_21") (pintype "bidirectional"))
    )
    (net (code "61") (name "unconnected-(U2-PB11-Pad22)") (class "Default")
      (node (ref "U2") (pin "22") (pinfunction "PB11_22") (pintype "bidirectional"))
    )
    (net (code "62") (name "unconnected-(U2-PB12-Pad25)") (class "Default")
      (node (ref "U2") (pin "25") (pinfunction "PB12_25") (pintype "bidirectional"))
    )
    (net (code "63") (name "unconnected-(U2-PB13-Pad26)") (class "Default")
      (node (ref "U2") (pin "26") (pinfunction "PB13_26") (pintype "bidirectional"))
    )
    (net (code "64") (name "unconnected-(U2-PB14-Pad27)") (class "Default")
      (node (ref "U2") (pin "27") (pinfunction "PB14_27") (pintype "bidirectional"))
    )
    (net (code "65") (name "unconnected-(U2-PB15-Pad28)") (class "Default")
      (node (ref "U2") (pin "28") (pinfunction "PB15_28") (pintype "bidirectional"))
    )
    (net (code "66") (name "unconnected-(U2-PC13-TAMPER-RTC-Pad2)") (class "Default")
      (node (ref "U2") (pin "2") (pinfunction "PC13-TAMPER-RTC_2") (pintype "bidirectional"))
    )
    (net (code "67") (name "unconnected-(U2-PC14-OSC32-IN-Pad3)") (class "Default")
      (node (ref "U2") (pin "3") (pinfunction "PC14-OSC32-IN_3") (pintype "bidirectional"))
    )
    (net (code "68") (name "unconnected-(U2-PC15-OSC32-OUT-Pad4)") (class "Default")
      (node (ref "U2") (pin "4") (pinfunction "PC15-OSC32-OUT_4") (pintype "bidirectional"))
    )
    (net (code "69") (name "unconnected-(U2-PF6-Pad35)") (class "Default")
      (node (ref "U2") (pin "35") (pinfunction "PF6_35") (pintype "power_in"))
    )
    (net (code "70") (name "unconnected-(U2-PF7-Pad36)") (class "Default")
      (node (ref "U2") (pin "36") (pinfunction "PF7_36") (pintype "power_in"))
    )
  )
)
